# ads1299.net
KiCad netlist of a schematic drawn in Altium Designer
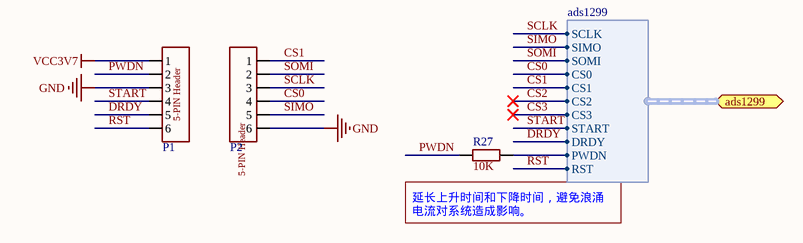
[diagram p0: ads1299.SchDoc]

(export (version "E")
  (design (tool "Eeschema 10.0.6"))
  (components
    (comp (ref "P1")
      (value "Header 6")
      (footprint "排母1X6 2.54MM")
      (description "Header, 6-Pin")
      (fields (field (name "PUBLISHER") "Altium Limited"))
      (libsource (lib "接插器件封装库") (part "排针/排母 1X6"))
    )
    (comp (ref "P2")
      (value "Header 6")
      (footprint "排母1X6 2.54MM")
      (description "Header, 6-Pin")
      (fields (field (name "PUBLISHER") "Altium Limited"))
      (libsource (lib "") (part "排针/排母 1X6_1"))
    )
    (comp (ref "R27")
      (value "10K")
      (footprint "R0402")
      (description "Register")
      (libsource (lib "电子元件封装库") (part "贴片电阻"))
    )
  )
  (nets
    (net (code "2") (name "/CS0") (class "Default")
      (node (ref "P2") (pin "4") (pinfunction "4_4") (pintype "passive"))
    )
    (net (code "3") (name "/CS1") (class "Default")
      (node (ref "P2") (pin "1") (pinfunction "1_1") (pintype "passive"))
    )
    (net (code "6") (name "/DRDY") (class "Default")
      (node (ref "P1") (pin "5") (pinfunction "5_5") (pintype "passive"))
    )
    (net (code "7") (name "/PWDN") (class "Default")
      (node (ref "P1") (pin "2") (pinfunction "2_2") (pintype "passive"))
      (node (ref "R27") (pin "1") (pinfunction "1_1") (pintype "passive"))
    )
    (net (code "8") (name "/RST") (class "Default")
      (node (ref "P1") (pin "6") (pinfunction "6_6") (pintype "passive"))
    )
    (net (code "9") (name "/SCLK") (class "Default")
      (node (ref "P2") (pin "3") (pinfunction "3_3") (pintype "passive"))
    )
    (net (code "10") (name "/SIMO") (class "Default")
      (node (ref "P2") (pin "5") (pinfunction "5_5") (pintype "passive"))
    )
    (net (code "11") (name "/SOMI") (class "Default")
      (node (ref "P2") (pin "2") (pinfunction "2_2") (pintype "passive"))
    )
    (net (code "12") (name "/START") (class "Default")
      (node (ref "P1") (pin "4") (pinfunction "4_4") (pintype "passive"))
    )
    (net (code "14") (name "GND") (class "Default")
      (node (ref "P1") (pin "3") (pinfunction "3_3") (pintype "passive"))
      (node (ref "P2") (pin "6") (pinfunction "6_6") (pintype "passive"))
    )
    (net (code "15") (name "VCC3V7") (class "Default")
      (node (ref "P1") (pin "1") (pinfunction "1_1") (pintype "passive"))
    )
    (net (code "16") (name "unconnected-(R27-Pad2)") (class "Default")
      (node (ref "R27") (pin "2") (pinfunction "2_2") (pintype "passive"))
    )
  )
)
